# MICRO_SD_CARD.net
KiCad netlist of a schematic drawn in Altium Designer
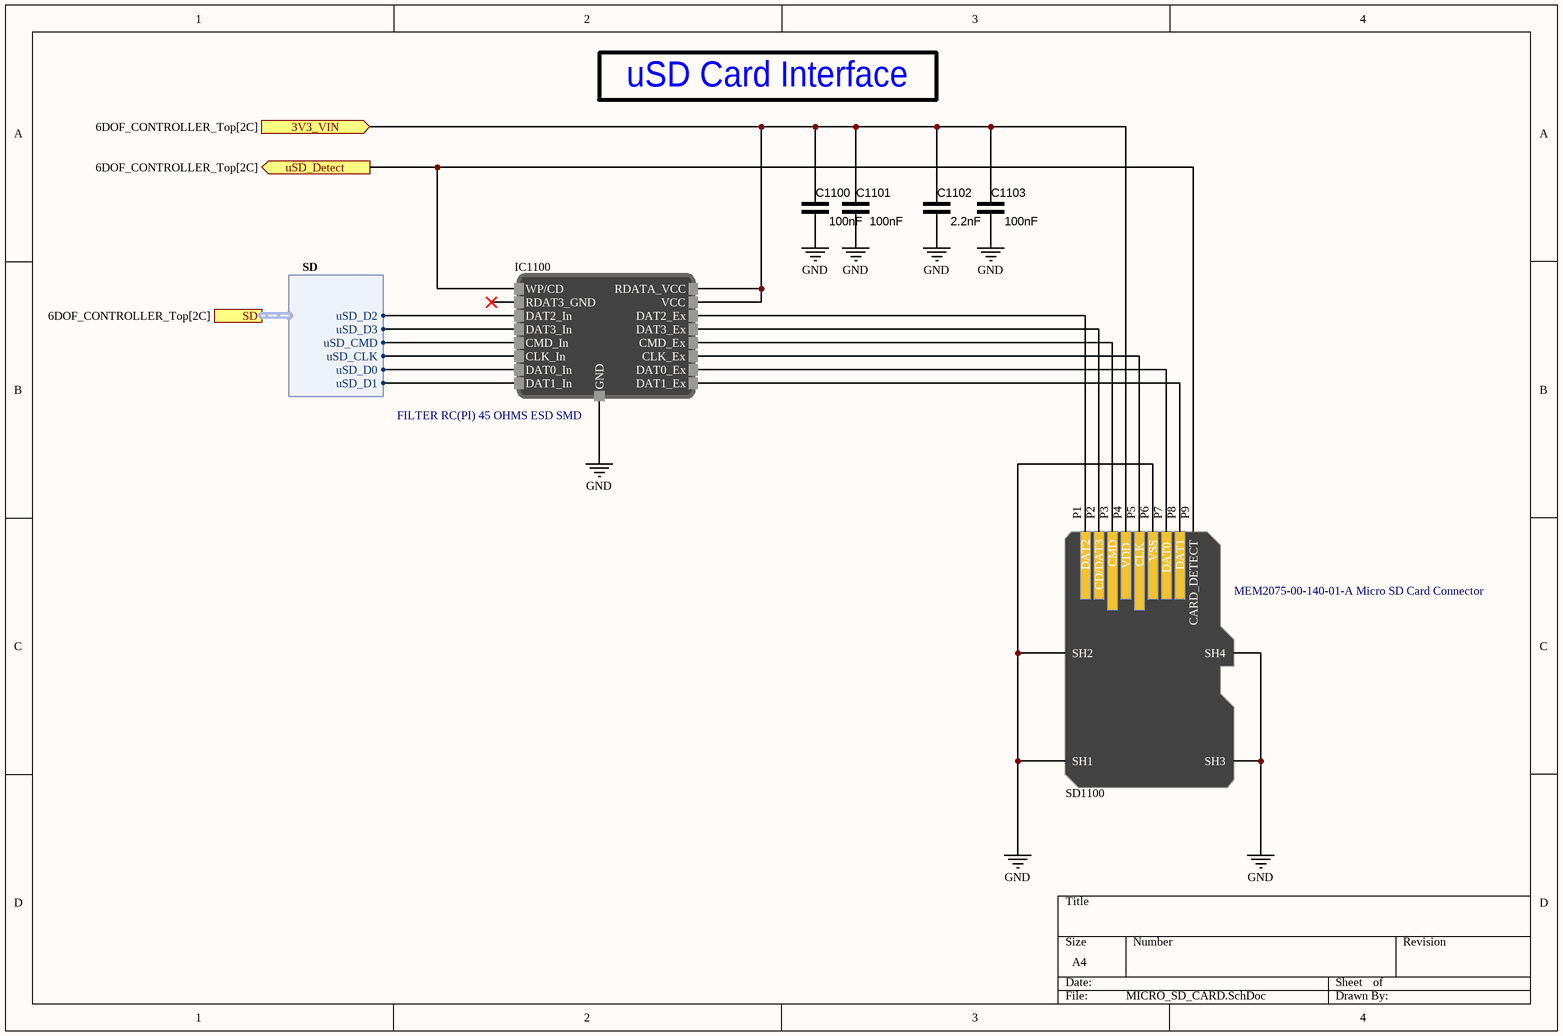
[diagram p0: MICRO_SD_CARD.SchDoc]

(export (version "E")
  (design (tool "Eeschema 10.0.6"))
  (components
    (comp (ref "C1100")
      (value "100nF")
      (footprint "CAP_0603")
      (description "0.1 µF ±10% 25V Ceramic Capacitor X7R 0603 (1608 Metric)")
      (fields (field (name "DIGIKEY PART NUMBER") "478-KAM15AR71E104KTCT-ND"))
      (libsource (lib "CapacitorsIntegrated") (part "C000007"))
    )
    (comp (ref "C1101")
      (value "100nF")
      (footprint "CAP_0603")
      (description "0.1 µF ±10% 25V Ceramic Capacitor X7R 0603 (1608 Metric)")
      (fields (field (name "DIGIKEY PART NUMBER") "478-KAM15AR71E104KTCT-ND"))
      (libsource (lib "CapacitorsIntegrated") (part "C000007"))
    )
    (comp (ref "C1102")
      (value "2.2nF")
      (footprint "CAP_0603")
      (description "2200 pF ±10% 25V Ceramic Capacitor X7R 0603 (1608 Metric)")
      (fields (field (name "DIGIKEY PART NUMBER") "311-3653-1-ND"))
      (libsource (lib "CapacitorsIntegrated") (part "C000006"))
    )
    (comp (ref "C1103")
      (value "100nF")
      (footprint "CAP_0603")
      (description "0.1 µF ±10% 25V Ceramic Capacitor X7R 0603 (1608 Metric)")
      (fields (field (name "DIGIKEY PART NUMBER") "478-KAM15AR71E104KTCT-ND"))
      (libsource (lib "CapacitorsIntegrated") (part "C000007"))
    )
    (comp (ref "IC1100")
      (value "FILTER RC(PI) 45 OHMS ESD SMD")
      (footprint "Micro QFN 3.5x1.2-16L")
      (description "RC (Pi) EMI Filter 2nd Order Low Pass 6 Channel R = 45Ohms, C = 20pF (Total) 16-UFDFN Exposed Pad")
      (fields (field (name "DIGIKEY PART NUMBER") "497-8751-1-ND"))
      (libsource (lib "IntegratedCircuits") (part "EMIF06-MSD02N16"))
    )
    (comp (ref "SD1100")
      (value "MEM2075-00-140-01-A Micro SD Card Connector")
      (footprint "uSD_CARD_9(8+1)")
      (description "9 (8 + 1) Position Card Connector Secure Digital - microSD™ Surface Mount, Right Angle Gold")
      (fields
        (field (name "DIGIKEY PART NUMBER") "2073-MEM2075-00-140-01-ACT-ND")
        (field (name "MOUSER PART NUMBER") "640-MEM20750014001A")
      )
      (libsource (lib "ElectroMechanical") (part "00000015"))
    )
  )
  (nets
    (net (code "2") (name "/3V3_VIN") (class "Default")
      (node (ref "C1100") (pin "2") (pinfunction "2_2") (pintype "passive"))
      (node (ref "C1101") (pin "2") (pinfunction "2_2") (pintype "passive"))
      (node (ref "C1102") (pin "2") (pinfunction "2_2") (pintype "passive"))
      (node (ref "C1103") (pin "2") (pinfunction "2_2") (pintype "passive"))
      (node (ref "IC1100") (pin "15") (pinfunction "VCC_15") (pintype "passive"))
      (node (ref "IC1100") (pin "16") (pinfunction "RDATA_VCC_16") (pintype "passive"))
      (node (ref "SD1100") (pin "P4") (pinfunction "VDD_P4") (pintype "passive"))
    )
    (net (code "3") (name "/uSD_CLK") (class "Default")
      (node (ref "IC1100") (pin "6") (pinfunction "CLK_In_6") (pintype "passive"))
    )
    (net (code "4") (name "/uSD_CMD") (class "Default")
      (node (ref "IC1100") (pin "5") (pinfunction "CMD_In_5") (pintype "passive"))
    )
    (net (code "5") (name "/uSD_D0") (class "Default")
      (node (ref "IC1100") (pin "7") (pinfunction "DAT0_In_7") (pintype "passive"))
    )
    (net (code "6") (name "/uSD_D1") (class "Default")
      (node (ref "IC1100") (pin "8") (pinfunction "DAT1_In_8") (pintype "passive"))
    )
    (net (code "7") (name "/uSD_D2") (class "Default")
      (node (ref "IC1100") (pin "3") (pinfunction "DAT2_In_3") (pintype "passive"))
    )
    (net (code "8") (name "/uSD_D3") (class "Default")
      (node (ref "IC1100") (pin "4") (pinfunction "DAT3_In_4") (pintype "passive"))
    )
    (net (code "9") (name "/uSD_Detect") (class "Default")
      (node (ref "IC1100") (pin "1") (pinfunction "WP/CD_1") (pintype "passive"))
      (node (ref "SD1100") (pin "P9") (pinfunction "CARD_DETECT_P9") (pintype "passive"))
    )
    (net (code "11") (name "GND") (class "Default")
      (node (ref "C1100") (pin "1") (pinfunction "1_1") (pintype "passive"))
      (node (ref "C1101") (pin "1") (pinfunction "1_1") (pintype "passive"))
      (node (ref "C1102") (pin "1") (pinfunction "1_1") (pintype "passive"))
      (node (ref "C1103") (pin "1") (pinfunction "1_1") (pintype "passive"))
      (node (ref "IC1100") (pin "17") (pinfunction "GND_17") (pintype "passive"))
      (node (ref "SD1100") (pin "P6") (pinfunction "VSS_P6") (pintype "passive"))
      (node (ref "SD1100") (pin "SH1") (pinfunction "SH1_SH1") (pintype "passive"))
      (node (ref "SD1100") (pin "SH2") (pinfunction "SH2_SH2") (pintype "passive"))
      (node (ref "SD1100") (pin "SH3") (pinfunction "SH3_SH3") (pintype "passive"))
      (node (ref "SD1100") (pin "SH4") (pinfunction "SH4_SH4") (pintype "passive"))
    )
    (net (code "12") (name "Net-(IC1100-CLK_Ex)") (class "Default")
      (node (ref "IC1100") (pin "11") (pinfunction "CLK_Ex_11") (pintype "passive"))
      (node (ref "SD1100") (pin "P5") (pinfunction "CLK_P5") (pintype "passive"))
    )
    (net (code "13") (name "Net-(IC1100-CMD_Ex)") (class "Default")
      (node (ref "IC1100") (pin "12") (pinfunction "CMD_Ex_12") (pintype "passive"))
      (node (ref "SD1100") (pin "P3") (pinfunction "CMD_P3") (pintype "passive"))
    )
    (net (code "14") (name "Net-(IC1100-DAT0_Ex)") (class "Default")
      (node (ref "IC1100") (pin "10") (pinfunction "DAT0_Ex_10") (pintype "passive"))
      (node (ref "SD1100") (pin "P7") (pinfunction "DAT0_P7") (pintype "passive"))
    )
    (net (code "15") (name "Net-(IC1100-DAT1_Ex)") (class "Default")
      (node (ref "IC1100") (pin "9") (pinfunction "DAT1_Ex_9") (pintype "passive"))
      (node (ref "SD1100") (pin "P8") (pinfunction "DAT1_P8") (pintype "passive"))
    )
    (net (code "16") (name "Net-(IC1100-DAT2_Ex)") (class "Default")
      (node (ref "IC1100") (pin "14") (pinfunction "DAT2_Ex_14") (pintype "passive"))
      (node (ref "SD1100") (pin "P1") (pinfunction "DAT2_P1") (pintype "passive"))
    )
    (net (code "17") (name "Net-(IC1100-DAT3_Ex)") (class "Default")
      (node (ref "IC1100") (pin "13") (pinfunction "DAT3_Ex_13") (pintype "passive"))
      (node (ref "SD1100") (pin "P2") (pinfunction "CD/DAT3_P2") (pintype "passive"))
    )
    (net (code "18") (name "unconnected-(IC1100-RDAT3_GND-Pad2)") (class "Default")
      (node (ref "IC1100") (pin "2") (pinfunction "RDAT3_GND_2") (pintype "passive+no_connect"))
    )
  )
)
